# galePCB.net
KiCad netlist of a schematic drawn in EAGLE
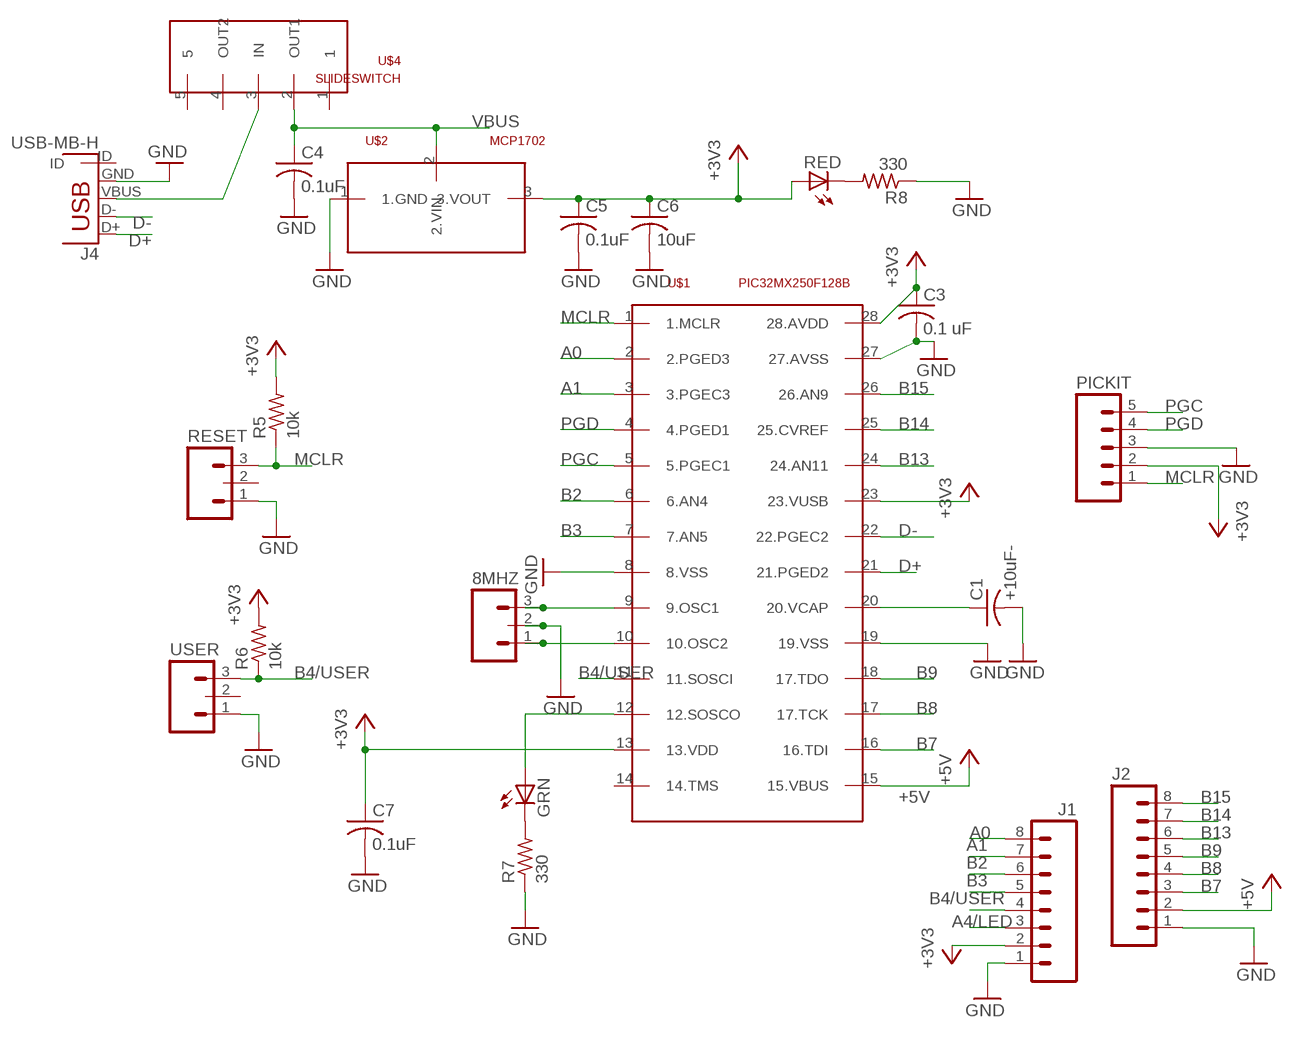
[diagram p0: schematic, sheet 1]

(export (version "E")
  (design (tool "Eeschema 10.0.6"))
  (components
    (comp (ref "8MHZ")
      (value "M03PTH")
      (footprint "eagle-import:1X03")
      (libsource (lib "eagle-import") (part "M03PTH"))
    )
    (comp (ref "C1")
      (value "+10uF-")
      (footprint "eagle-import:C025-024X044")
      (libsource (lib "eagle-import") (part "C-US025-024X044"))
    )
    (comp (ref "C3")
      (value "0.1 uF")
      (footprint "eagle-import:C025-024X044")
      (libsource (lib "eagle-import") (part "C-US025-024X044"))
    )
    (comp (ref "C4")
      (value "0.1uF")
      (footprint "eagle-import:C025-024X044")
      (libsource (lib "eagle-import") (part "C-US025-024X044"))
    )
    (comp (ref "C5")
      (value "0.1uF")
      (footprint "eagle-import:C025-024X044")
      (libsource (lib "eagle-import") (part "C-US025-024X044"))
    )
    (comp (ref "C6")
      (value "10uF")
      (footprint "eagle-import:C025-024X044")
      (libsource (lib "eagle-import") (part "C-US025-024X044"))
    )
    (comp (ref "C7")
      (value "0.1uF")
      (footprint "eagle-import:C025-024X044")
      (libsource (lib "eagle-import") (part "C-US025-024X044"))
    )
    (comp (ref "GRN")
      (value "LED3MM")
      (footprint "eagle-import:LED3MM")
      (libsource (lib "eagle-import") (part "LED3MM"))
    )
    (comp (ref "J1")
      (value "M08")
      (footprint "eagle-import:1X08_ROUND")
      (libsource (lib "eagle-import") (part "M08"))
    )
    (comp (ref "J2")
      (value "M08")
      (footprint "eagle-import:1X08_ROUND")
      (libsource (lib "eagle-import") (part "M08"))
    )
    (comp (ref "J4")
      (value "USB-MB-H")
      (footprint "eagle-import:USB-MB-H")
      (libsource (lib "eagle-import") (part "USB-MB-H"))
    )
    (comp (ref "PICKIT")
      (value "M05PTH")
      (footprint "eagle-import:1X05")
      (libsource (lib "eagle-import") (part "M05PTH"))
    )
    (comp (ref "R5")
      (value "10k")
      (footprint "eagle-import:0207_10")
      (libsource (lib "eagle-import") (part "R-US_0207/10"))
    )
    (comp (ref "R6")
      (value "10k")
      (footprint "eagle-import:0207_10")
      (libsource (lib "eagle-import") (part "R-US_0207/10"))
    )
    (comp (ref "R7")
      (value "330")
      (footprint "eagle-import:0207_10")
      (libsource (lib "eagle-import") (part "R-US_0207/10"))
    )
    (comp (ref "R8")
      (value "330")
      (footprint "eagle-import:0207_10")
      (libsource (lib "eagle-import") (part "R-US_0207/10"))
    )
    (comp (ref "RED")
      (value "LED3MM")
      (footprint "eagle-import:LED3MM")
      (libsource (lib "eagle-import") (part "LED3MM"))
    )
    (comp (ref "RESET")
      (value "M03LOCK")
      (footprint "eagle-import:1X03_LOCK")
      (libsource (lib "eagle-import") (part "M03LOCK"))
    )
    (comp (ref "U$1")
      (value "PIC32MX250F128B")
      (footprint "eagle-import:DIL28-3")
      (libsource (lib "eagle-import") (part "PIC32"))
    )
    (comp (ref "U$2")
      (value "MCP1702")
      (footprint "eagle-import:TO92")
      (libsource (lib "eagle-import") (part "MCP1702"))
    )
    (comp (ref "U$4")
      (value "SLIDESWITCH")
      (footprint "eagle-import:SLIDESWITCH")
      (libsource (lib "eagle-import") (part "SLIDESWITCH"))
    )
    (comp (ref "USER")
      (value "M03LOCK")
      (footprint "eagle-import:1X03_LOCK")
      (libsource (lib "eagle-import") (part "M03LOCK"))
    )
  )
  (nets
    (net (code "1") (name "+3V3") (class "Default")
      (node (ref "C3") (pin "1") (pinfunction "1_1") (pintype "passive"))
      (node (ref "C5") (pin "1") (pinfunction "1_1") (pintype "passive"))
      (node (ref "C6") (pin "1") (pinfunction "1_1") (pintype "passive"))
      (node (ref "C7") (pin "1") (pinfunction "1_1") (pintype "passive"))
      (node (ref "J1") (pin "2") (pinfunction "2_2") (pintype "passive"))
      (node (ref "PICKIT") (pin "2") (pinfunction "2_2") (pintype "passive"))
      (node (ref "R5") (pin "2") (pinfunction "2_2") (pintype "passive"))
      (node (ref "R6") (pin "2") (pinfunction "2_2") (pintype "passive"))
      (node (ref "RED") (pin "A") (pinfunction "A_A") (pintype "passive"))
      (node (ref "U$1") (pin "13") (pinfunction "13.VDD_13") (pintype "bidirectional"))
      (node (ref "U$1") (pin "23") (pinfunction "23.VUSB_23") (pintype "bidirectional"))
      (node (ref "U$1") (pin "28") (pinfunction "28.AVDD_28") (pintype "bidirectional"))
      (node (ref "U$2") (pin "3") (pinfunction "3.VOUT_3") (pintype "bidirectional"))
    )
    (net (code "2") (name "+5V") (class "Default")
      (node (ref "J2") (pin "2") (pinfunction "2_2") (pintype "passive"))
      (node (ref "U$1") (pin "15") (pinfunction "15.VBUS_15") (pintype "bidirectional"))
    )
    (net (code "3") (name "/A0") (class "Default")
      (node (ref "J1") (pin "8") (pinfunction "8_8") (pintype "passive"))
      (node (ref "U$1") (pin "2") (pinfunction "2.PGED3_2") (pintype "bidirectional"))
    )
    (net (code "4") (name "/A1") (class "Default")
      (node (ref "J1") (pin "7") (pinfunction "7_7") (pintype "passive"))
      (node (ref "U$1") (pin "3") (pinfunction "3.PGEC3_3") (pintype "bidirectional"))
    )
    (net (code "5") (name "/A4{slash}LED") (class "Default")
      (node (ref "GRN") (pin "A") (pinfunction "A_A") (pintype "passive"))
      (node (ref "J1") (pin "3") (pinfunction "3_3") (pintype "passive"))
      (node (ref "U$1") (pin "12") (pinfunction "12.SOSCO_12") (pintype "bidirectional"))
    )
    (net (code "6") (name "/B2") (class "Default")
      (node (ref "J1") (pin "6") (pinfunction "6_6") (pintype "passive"))
      (node (ref "U$1") (pin "6") (pinfunction "6.AN4_6") (pintype "bidirectional"))
    )
    (net (code "7") (name "/B3") (class "Default")
      (node (ref "J1") (pin "5") (pinfunction "5_5") (pintype "passive"))
      (node (ref "U$1") (pin "7") (pinfunction "7.AN5_7") (pintype "bidirectional"))
    )
    (net (code "8") (name "/B4{slash}USER") (class "Default")
      (node (ref "J1") (pin "4") (pinfunction "4_4") (pintype "passive"))
      (node (ref "R6") (pin "1") (pinfunction "1_1") (pintype "passive"))
      (node (ref "U$1") (pin "11") (pinfunction "11.SOSCI_11") (pintype "bidirectional"))
      (node (ref "USER") (pin "3") (pinfunction "3_3") (pintype "passive"))
    )
    (net (code "9") (name "/B7") (class "Default")
      (node (ref "J2") (pin "3") (pinfunction "3_3") (pintype "passive"))
      (node (ref "U$1") (pin "16") (pinfunction "16.TDI_16") (pintype "bidirectional"))
    )
    (net (code "10") (name "/B8") (class "Default")
      (node (ref "J2") (pin "4") (pinfunction "4_4") (pintype "passive"))
      (node (ref "U$1") (pin "17") (pinfunction "17.TCK_17") (pintype "bidirectional"))
    )
    (net (code "11") (name "/B9") (class "Default")
      (node (ref "J2") (pin "5") (pinfunction "5_5") (pintype "passive"))
      (node (ref "U$1") (pin "18") (pinfunction "17.TDO_18") (pintype "bidirectional"))
    )
    (net (code "12") (name "/B13") (class "Default")
      (node (ref "J2") (pin "6") (pinfunction "6_6") (pintype "passive"))
      (node (ref "U$1") (pin "24") (pinfunction "24.AN11_24") (pintype "bidirectional"))
    )
    (net (code "13") (name "/B14") (class "Default")
      (node (ref "J2") (pin "7") (pinfunction "7_7") (pintype "passive"))
      (node (ref "U$1") (pin "25") (pinfunction "25.CVREF_25") (pintype "bidirectional"))
    )
    (net (code "14") (name "/B15") (class "Default")
      (node (ref "J2") (pin "8") (pinfunction "8_8") (pintype "passive"))
      (node (ref "U$1") (pin "26") (pinfunction "26.AN9_26") (pintype "bidirectional"))
    )
    (net (code "15") (name "/D+") (class "Default")
      (node (ref "J4") (pin "D+") (pinfunction "D+_D+") (pintype "bidirectional"))
      (node (ref "U$1") (pin "21") (pinfunction "21.PGED2_21") (pintype "bidirectional"))
    )
    (net (code "16") (name "/D-") (class "Default")
      (node (ref "J4") (pin "D-") (pinfunction "D-_D-") (pintype "bidirectional"))
      (node (ref "U$1") (pin "22") (pinfunction "22.PGEC2_22") (pintype "bidirectional"))
    )
    (net (code "17") (name "/MCLR") (class "Default")
      (node (ref "PICKIT") (pin "1") (pinfunction "1_1") (pintype "passive"))
      (node (ref "R5") (pin "1") (pinfunction "1_1") (pintype "passive"))
      (node (ref "RESET") (pin "3") (pinfunction "3_3") (pintype "passive"))
      (node (ref "U$1") (pin "1") (pinfunction "1.MCLR_1") (pintype "bidirectional"))
    )
    (net (code "18") (name "/PGC") (class "Default")
      (node (ref "PICKIT") (pin "5") (pinfunction "5_5") (pintype "passive"))
      (node (ref "U$1") (pin "5") (pinfunction "5.PGEC1_5") (pintype "bidirectional"))
    )
    (net (code "19") (name "/PGD") (class "Default")
      (node (ref "PICKIT") (pin "4") (pinfunction "4_4") (pintype "passive"))
      (node (ref "U$1") (pin "4") (pinfunction "4.PGED1_4") (pintype "bidirectional"))
    )
    (net (code "20") (name "/VBUS") (class "Default")
      (node (ref "C4") (pin "1") (pinfunction "1_1") (pintype "passive"))
      (node (ref "J4") (pin "VBUS") (pinfunction "VBUS_VBUS") (pintype "bidirectional"))
      (node (ref "U$2") (pin "2") (pinfunction "2.VIN_2") (pintype "bidirectional"))
      (node (ref "U$4") (pin "2") (pinfunction "OUT1_2") (pintype "bidirectional"))
      (node (ref "U$4") (pin "3") (pinfunction "IN_3") (pintype "bidirectional"))
    )
    (net (code "21") (name "GND") (class "Default")
      (node (ref "8MHZ") (pin "2") (pinfunction "2_2") (pintype "passive"))
      (node (ref "C1") (pin "2") (pinfunction "2_2") (pintype "passive"))
      (node (ref "C3") (pin "2") (pinfunction "2_2") (pintype "passive"))
      (node (ref "C4") (pin "2") (pinfunction "2_2") (pintype "passive"))
      (node (ref "C5") (pin "2") (pinfunction "2_2") (pintype "passive"))
      (node (ref "C6") (pin "2") (pinfunction "2_2") (pintype "passive"))
      (node (ref "C7") (pin "2") (pinfunction "2_2") (pintype "passive"))
      (node (ref "J1") (pin "1") (pinfunction "1_1") (pintype "passive"))
      (node (ref "J2") (pin "1") (pinfunction "1_1") (pintype "passive"))
      (node (ref "J4") (pin "GND") (pinfunction "GND_GND") (pintype "bidirectional"))
      (node (ref "PICKIT") (pin "3") (pinfunction "3_3") (pintype "passive"))
      (node (ref "R7") (pin "1") (pinfunction "1_1") (pintype "passive"))
      (node (ref "R8") (pin "1") (pinfunction "1_1") (pintype "passive"))
      (node (ref "RESET") (pin "1") (pinfunction "1_1") (pintype "passive"))
      (node (ref "U$1") (pin "19") (pinfunction "19.VSS_19") (pintype "bidirectional"))
      (node (ref "U$1") (pin "27") (pinfunction "27.AVSS_27") (pintype "bidirectional"))
      (node (ref "U$1") (pin "8") (pinfunction "8.VSS_8") (pintype "bidirectional"))
      (node (ref "U$2") (pin "1") (pinfunction "1.GND_1") (pintype "bidirectional"))
      (node (ref "USER") (pin "1") (pinfunction "1_1") (pintype "passive"))
    )
    (net (code "22") (name "Net-(GRN-C)") (class "Default")
      (node (ref "GRN") (pin "K") (pinfunction "C_K") (pintype "passive"))
      (node (ref "R7") (pin "2") (pinfunction "2_2") (pintype "passive"))
    )
    (net (code "23") (name "Net-(RED-C)") (class "Default")
      (node (ref "R8") (pin "2") (pinfunction "2_2") (pintype "passive"))
      (node (ref "RED") (pin "K") (pinfunction "C_K") (pintype "passive"))
    )
    (net (code "24") (name "Net-(U$1-9.OSC1)") (class "Default")
      (node (ref "8MHZ") (pin "3") (pinfunction "3_3") (pintype "passive"))
      (node (ref "U$1") (pin "9") (pinfunction "9.OSC1_9") (pintype "bidirectional"))
    )
    (net (code "25") (name "Net-(U$1-10.OSC2)") (class "Default")
      (node (ref "8MHZ") (pin "1") (pinfunction "1_1") (pintype "passive"))
      (node (ref "U$1") (pin "10") (pinfunction "10.OSC2_10") (pintype "bidirectional"))
    )
    (net (code "26") (name "Net-(U$1-20.VCAP)") (class "Default")
      (node (ref "C1") (pin "1") (pinfunction "1_1") (pintype "passive"))
      (node (ref "U$1") (pin "20") (pinfunction "20.VCAP_20") (pintype "bidirectional"))
    )
    (net (code "27") (name "unconnected-(J4-PadID)") (class "Default")
      (node (ref "J4") (pin "ID") (pinfunction "ID_ID") (pintype "bidirectional"))
    )
    (net (code "28") (name "unconnected-(RESET-Pad2)") (class "Default")
      (node (ref "RESET") (pin "2") (pinfunction "2_2") (pintype "passive"))
    )
    (net (code "29") (name "unconnected-(U$1-14.TMS-Pad14)") (class "Default")
      (node (ref "U$1") (pin "14") (pinfunction "14.TMS_14") (pintype "bidirectional"))
    )
    (net (code "30") (name "unconnected-(U$4-OUT2-Pad4)") (class "Default")
      (node (ref "U$4") (pin "4") (pinfunction "OUT2_4") (pintype "bidirectional"))
    )
    (net (code "31") (name "unconnected-(U$4-Pad1)") (class "Default")
      (node (ref "U$4") (pin "1") (pinfunction "1_1") (pintype "bidirectional"))
    )
    (net (code "32") (name "unconnected-(U$4-Pad5)") (class "Default")
      (node (ref "U$4") (pin "5") (pinfunction "5_5") (pintype "bidirectional"))
    )
    (net (code "33") (name "unconnected-(USER-Pad2)") (class "Default")
      (node (ref "USER") (pin "2") (pinfunction "2_2") (pintype "passive"))
    )
  )
)
